# Sheet1.net
KiCad netlist of a schematic drawn in Altium Designer
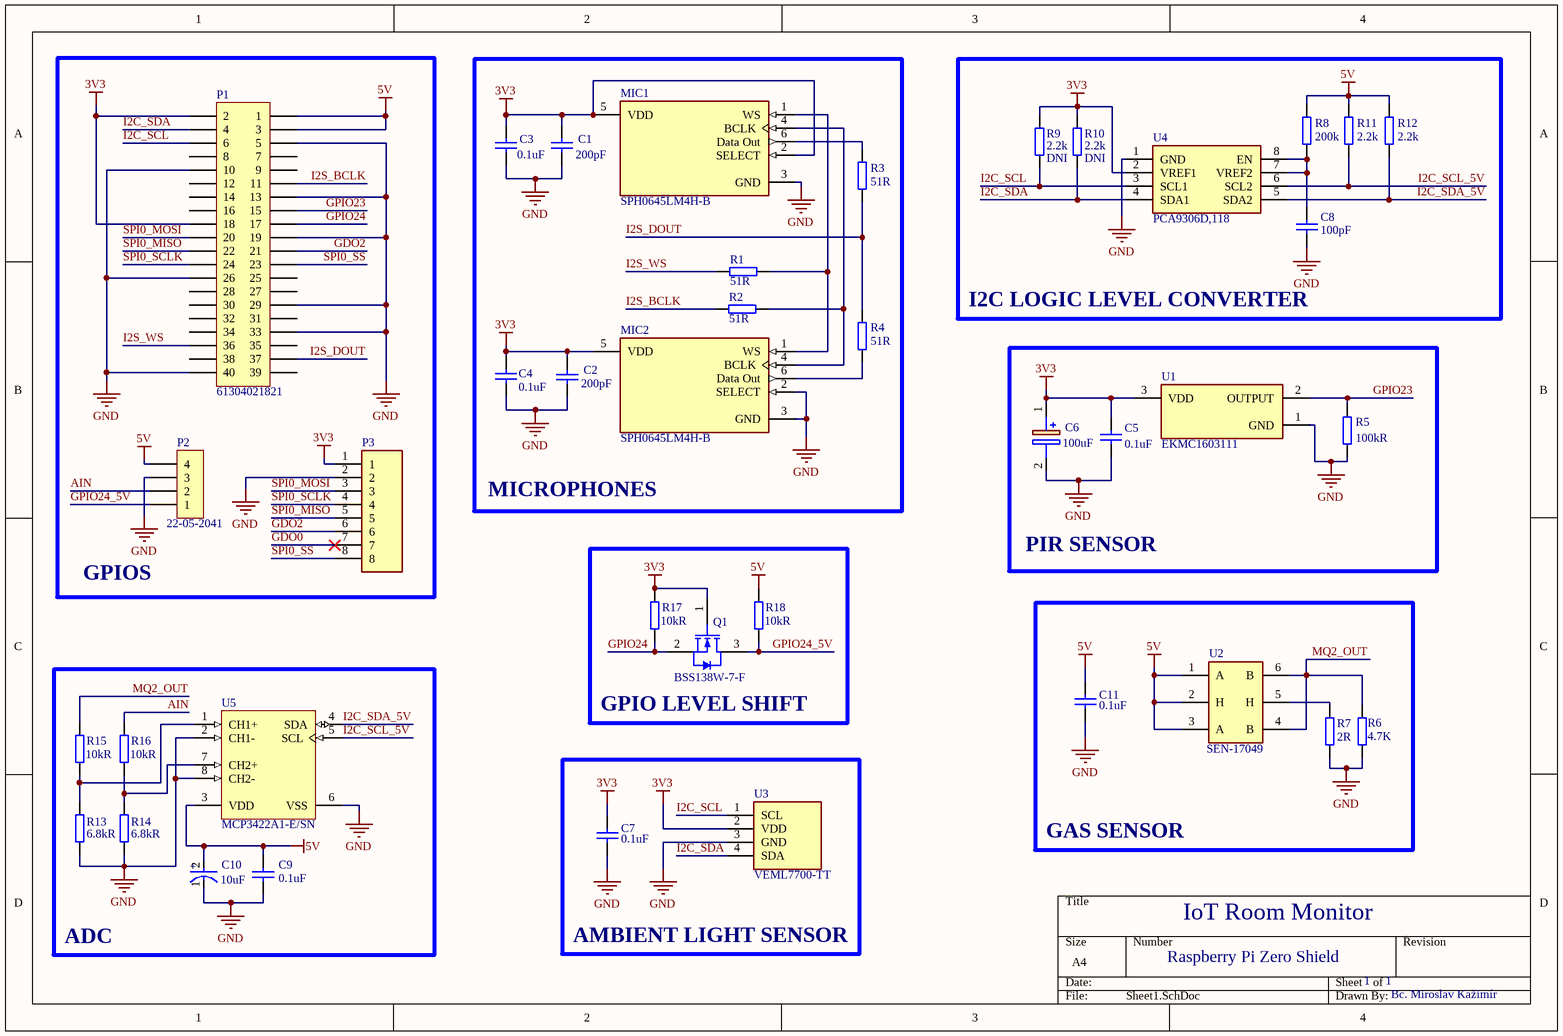
[diagram p0: Sheet1.SchDoc]

(export (version "E")
  (design (tool "Eeschema 10.0.6"))
  (components
    (comp (ref "C1")
      (value "C1206C201F4HACTU")
      (footprint "FP-C1206C-EB-MFG")
      (fields (field (name "MANUFACTURER") "KEMET") (field (name "CAPACITANCE") "200pF"))
      (libsource (lib "RPiZeroShield") (part "C1206C201F4HACTU"))
    )
    (comp (ref "C2")
      (value "C1206C201F4HACTU")
      (footprint "FP-C1206C-EB-MFG")
      (fields (field (name "MANUFACTURER") "KEMET") (field (name "CAPACITANCE") "200pF"))
      (libsource (lib "RPiZeroShield") (part "C1206C201F4HACTU"))
    )
    (comp (ref "C3")
      (value "GRM3195C1H104GA05D")
      (footprint "FP-GRM319-0_15-IPC_A")
      (description "Multi-Layer Ceramic Capacitor 0.1uF C0G 2% 1206 Paper T/R")
      (fields (field (name "MANUFACTURER") "Murata") (field (name "CAPACITANCE") "0.1uF"))
      (libsource (lib "RPiZeroShield") (part "GRM3195C1H104GA05D"))
    )
    (comp (ref "C4")
      (value "GRM3195C1H104GA05D")
      (footprint "FP-GRM319-0_15-IPC_A")
      (description "Multi-Layer Ceramic Capacitor 0.1uF C0G 2% 1206 Paper T/R")
      (fields (field (name "MANUFACTURER") "Murata") (field (name "CAPACITANCE") "0.1uF"))
      (libsource (lib "RPiZeroShield") (part "GRM3195C1H104GA05D"))
    )
    (comp (ref "C5")
      (value "GRM3195C1H104GA05D")
      (footprint "FP-GRM319-0_15-IPC_A")
      (description "Multi-Layer Ceramic Capacitor 0.1uF C0G 2% 1206 Paper T/R")
      (fields (field (name "MANUFACTURER") "Murata") (field (name "CAPACITANCE") "0.1uF"))
      (libsource (lib "RPiZeroShield") (part "GRM3195C1H104GA05D"))
    )
    (comp (ref "C6")
      (value "ECE-A0JKS101B")
      (footprint "CAPPRD250W50D630H600")
      (description "Cap Aluminum 100uF 6.3V 20% (6.3 X 5mm) Radial 5mm 71mA 1000 hr 85°C Ammo Pack")
      (fields
        (field (name "MANUFACTURER") "Panasonic")
        (field (name "CAPACITANCE") "100uF")
        (field (name "TOLERANCE") "20%")
      )
      (libsource (lib "RPiZeroShield") (part "ECE-A0JKS101B"))
    )
    (comp (ref "C7")
      (value "GRM3195C1H104GA05D")
      (footprint "FP-GRM319-0_15-IPC_A")
      (description "Multi-Layer Ceramic Capacitor 0.1uF C0G 2% 1206 Paper T/R")
      (fields (field (name "MANUFACTURER") "Murata") (field (name "CAPACITANCE") "0.1uF"))
      (libsource (lib "RPiZeroShield") (part "GRM3195C1H104GA05D"))
    )
    (comp (ref "C8")
      (value "C0805C101F3HACTU")
      (footprint "FP-C0805C-DN-IPC_A")
      (description "100.pf 25.0V Rohs Compliant: Yes")
      (fields (field (name "MANUFACTURER") "KEMET") (field (name "CAPACITANCE") "100pF"))
      (libsource (lib "RPiZeroShield") (part "C0805C101F3HACTU"))
    )
    (comp (ref "C9")
      (value "GRM3195C1H104GA05D")
      (footprint "FP-GRM319-0_15-IPC_A")
      (description "Multi-Layer Ceramic Capacitor 0.1uF C0G 2% 1206 Paper T/R")
      (fields (field (name "MANUFACTURER") "Murata") (field (name "CAPACITANCE") "0.1uF"))
      (libsource (lib "RPiZeroShield") (part "GRM3195C1H104GA05D"))
    )
    (comp (ref "C10")
      (value "T491A106K020AT")
      (footprint "FP-T491A106K020AT-MFG")
      (description "Cap Tant Solid 10uF 20V A CASE 10% (3.2 X 1.6 X 1.6mm) Inward L SMD 3216-18 5 Ohm 125°C T/R")
      (fields
        (field (name "MANUFACTURER") "KEMET")
        (field (name "CAPACITANCE") "10uF")
        (field (name "TOLERANCE") "10%")
      )
      (libsource (lib "RPiZeroShield") (part "T491A106K020AT"))
    )
    (comp (ref "C11")
      (value "GRM3195C1H104GA05D")
      (footprint "FP-GRM319-0_15-IPC_A")
      (description "Multi-Layer Ceramic Capacitor 0.1uF C0G 2% 1206 Paper T/R")
      (fields (field (name "MANUFACTURER") "Murata") (field (name "CAPACITANCE") "0.1uF"))
      (libsource (lib "RPiZeroShield") (part "GRM3195C1H104GA05D"))
    )
    (comp (ref "MIC1")
      (value "SPH0645LM4H-B")
      (footprint "FP-SPH0645LM4H-B-MFG")
      (description "Crawford Mic Dgt I2S Bottom Port")
      (fields (field (name "MANUFACTURER") "Knowles"))
      (libsource (lib "RPiZeroShield") (part "SPH0645LM4H-B"))
    )
    (comp (ref "MIC2")
      (value "SPH0645LM4H-B")
      (footprint "FP-SPH0645LM4H-B-MFG")
      (description "Crawford Mic Dgt I2S Bottom Port")
      (fields (field (name "MANUFACTURER") "Knowles"))
      (libsource (lib "RPiZeroShield") (part "SPH0645LM4H-B"))
    )
    (comp (ref "P1")
      (value "61304021821")
      (footprint "61304021821")
      (description "THT Vertical Socket Header WR-PHD, Pitch 2.54 mm, Dual Row, 40 pins")
      (fields (field (name "MANUFACTURER") "Wurth Electronics"))
      (libsource (lib "RPiZeroShield") (part "61304021821"))
    )
    (comp (ref "P2")
      (value "22-05-2041")
      (footprint "22052041")
      (description "Connector Unshrouded Header 4 Position 2.54mm Solder Right Angle Thru-Hole Bulk")
      (fields (field (name "MANUFACTURER") "Molex"))
      (libsource (lib "RPiZeroShield") (part "22-05-2041"))
    )
    (comp (ref "P3")
      (value "M22-2010805")
      (footprint "HDRV8W60P0X200_1X8_1600X200X525P")
      (description "Connector, Header, 8Pos, 1Row, 2Mm Rohs Compliant: Yes")
      (fields (field (name "MANUFACTURER") "Harwin"))
      (libsource (lib "RPiZeroShield") (part "M22-2010805"))
    )
    (comp (ref "Q1")
      (value "BSS138W-7-F")
      (footprint "DIOD-SOT323-3_V")
      (description "N沟道 VDS=50V VGS=±20V ID=200mA P=200mW")
      (fields (field (name "MANUFACTURER") "Diodes") (field (name "VOLTAGE") "50V"))
      (libsource (lib "RPiZeroShield") (part "BSS138W-7-F"))
    )
    (comp (ref "R1")
      (value "ERJ-6ENF51R0V")
      (footprint "RESC2013X70X40LL20T20")
      (description "贴片电阻 51Ω ±1% 1/8W ±100ppm/℃ 0805")
      (fields
        (field (name "MANUFACTURER") "Panasonic")
        (field (name "TOLERANCE") "1%")
        (field (name "RESISTANCE") "51R")
      )
      (libsource (lib "RPiZeroShield") (part "ERJ-6ENF51R0V"))
    )
    (comp (ref "R2")
      (value "ERJ-6ENF51R0V")
      (footprint "RESC2013X70X40LL20T20")
      (description "贴片电阻 51Ω ±1% 1/8W ±100ppm/℃ 0805")
      (fields
        (field (name "MANUFACTURER") "Panasonic")
        (field (name "TOLERANCE") "1%")
        (field (name "RESISTANCE") "51R")
      )
      (libsource (lib "RPiZeroShield") (part "ERJ-6ENF51R0V"))
    )
    (comp (ref "R3")
      (value "ERJ-6ENF51R0V")
      (footprint "RESC2013X70X40LL20T20")
      (description "贴片电阻 51Ω ±1% 1/8W ±100ppm/℃ 0805")
      (fields
        (field (name "MANUFACTURER") "Panasonic")
        (field (name "TOLERANCE") "1%")
        (field (name "RESISTANCE") "51R")
      )
      (libsource (lib "") (part "ERJ-6ENF51R0V_1"))
    )
    (comp (ref "R4")
      (value "ERJ-6ENF51R0V")
      (footprint "RESC2013X70X40LL20T20")
      (description "贴片电阻 51Ω ±1% 1/8W ±100ppm/℃ 0805")
      (fields
        (field (name "MANUFACTURER") "Panasonic")
        (field (name "TOLERANCE") "1%")
        (field (name "RESISTANCE") "51R")
      )
      (libsource (lib "") (part "ERJ-6ENF51R0V_2"))
    )
    (comp (ref "R5")
      (value "RC1206FR-07100KL")
      (footprint "RESC3116X65X40LL10T20")
      (description "贴片电阻 100000Ω ± 1.00% 0.25W ± 100ppm/℃ 1206")
      (fields
        (field (name "MANUFACTURER") "Yageo")
        (field (name "TOLERANCE") "1%")
        (field (name "RESISTANCE") "100kR")
      )
      (libsource (lib "RPiZeroShield") (part "RC1206FR-07100KL"))
    )
    (comp (ref "R6")
      (value "RCC12064K70FKEA")
      (footprint "RCC1206_e3")
      (description "Res, 4K7, 1%, 0.5W, 1206, Thick Film;")
      (fields (field (name "MANUFACTURER") "Vishay") (field (name "RESISTANCE") "4.7K"))
      (libsource (lib "RPiZeroShield") (part "RCC12064K70FKEA"))
    )
    (comp (ref "R7")
      (value "RC1206JR-7W2RL")
      (footprint "RESC3116X65N")
      (description "Res Thick Film 1206 2 Ohm 5% 0.5W(1/2W) ±200ppm/C Pad SMD T/R")
      (fields
        (field (name "MANUFACTURER") "Yageo")
        (field (name "RESISTANCE") "2R")
        (field (name "TOLERANCE") "5%")
      )
      (libsource (lib "RPiZeroShield") (part "RC1206JR-7W2RL"))
    )
    (comp (ref "R8")
      (value "RCC1206200KFKEA")
      (footprint "RCC1206_e3")
      (description "Res, AEC-Q200, 200K, 1%, 0.5W, 1206 Rohs Compliant: Yes")
      (fields (field (name "MANUFACTURER") "Vishay") (field (name "RESISTANCE") "200k"))
      (libsource (lib "RPiZeroShield") (part "RCC1206200KFKEA"))
    )
    (comp (ref "R9")
      (value "RCC12062K20FKEA")
      (footprint "RCC1206_e3")
      (description "Res, Aec-Q200, 2K2, 1%, 0.5W, 1206 Rohs Compliant: Yes")
      (fields (field (name "MANUFACTURER") "Vishay") (field (name "RESISTANCE") "2.2k"))
      (libsource (lib "RPiZeroShield") (part "RCC12062K20FKEA"))
    )
    (comp (ref "R10")
      (value "RCC12062K20FKEA")
      (footprint "RCC1206_e3")
      (description "Res, Aec-Q200, 2K2, 1%, 0.5W, 1206 Rohs Compliant: Yes")
      (fields (field (name "MANUFACTURER") "Vishay") (field (name "RESISTANCE") "2.2k"))
      (libsource (lib "RPiZeroShield") (part "RCC12062K20FKEA"))
    )
    (comp (ref "R11")
      (value "RCC12062K20FKEA")
      (footprint "RCC1206_e3")
      (description "Res, Aec-Q200, 2K2, 1%, 0.5W, 1206 Rohs Compliant: Yes")
      (fields (field (name "MANUFACTURER") "Vishay") (field (name "RESISTANCE") "2.2k"))
      (libsource (lib "RPiZeroShield") (part "RCC12062K20FKEA"))
    )
    (comp (ref "R12")
      (value "RCC12062K20FKEA")
      (footprint "RCC1206_e3")
      (description "Res, Aec-Q200, 2K2, 1%, 0.5W, 1206 Rohs Compliant: Yes")
      (fields (field (name "MANUFACTURER") "Vishay") (field (name "RESISTANCE") "2.2k"))
      (libsource (lib "RPiZeroShield") (part "RCC12062K20FKEA"))
    )
    (comp (ref "R13")
      (value "ERJ-P06D6801V")
      (footprint "ERJP06_(0805)")
      (description "Res Thick Film 0805 6.8K Ohm 0.5% 0.25W ±100ppm/°C Molded SMD Punched Carrier T/R")
      (fields
        (field (name "MANUFACTURER") "Panasonic")
        (field (name "RESISTANCE") "6.8kR")
        (field (name "TOLERANCE") "0.5%")
      )
      (libsource (lib "RPiZeroShield") (part "ERJ-P06D6801V"))
    )
    (comp (ref "R14")
      (value "ERJ-P06D6801V")
      (footprint "ERJP06_(0805)")
      (description "Res Thick Film 0805 6.8K Ohm 0.5% 0.25W ±100ppm/°C Molded SMD Punched Carrier T/R")
      (fields
        (field (name "MANUFACTURER") "Panasonic")
        (field (name "RESISTANCE") "6.8kR")
        (field (name "TOLERANCE") "0.5%")
      )
      (libsource (lib "RPiZeroShield") (part "ERJ-P06D6801V"))
    )
    (comp (ref "R15")
      (value "ERJ-P08D1002V")
      (footprint "ERJP08_(1206)")
      (description "Res Thick Film 1206 10K Ohm 0.5% 0.33W ±100ppm/°C Molded SMD Punched Carrier T/R")
      (fields
        (field (name "MANUFACTURER") "Panasonic")
        (field (name "RESISTANCE") "10kR")
        (field (name "TOLERANCE") "0.5%")
      )
      (libsource (lib "RPiZeroShield") (part "ERJ-P08D1002V"))
    )
    (comp (ref "R16")
      (value "ERJ-P08D1002V")
      (footprint "ERJP08_(1206)")
      (description "Res Thick Film 1206 10K Ohm 0.5% 0.33W ±100ppm/°C Molded SMD Punched Carrier T/R")
      (fields
        (field (name "MANUFACTURER") "Panasonic")
        (field (name "RESISTANCE") "10kR")
        (field (name "TOLERANCE") "0.5%")
      )
      (libsource (lib "RPiZeroShield") (part "ERJ-P08D1002V"))
    )
    (comp (ref "R17")
      (value "ERJ-P08D1002V")
      (footprint "ERJP08_(1206)")
      (description "Res Thick Film 1206 10K Ohm 0.5% 0.33W ±100ppm/°C Molded SMD Punched Carrier T/R")
      (fields
        (field (name "MANUFACTURER") "Panasonic")
        (field (name "RESISTANCE") "10kR")
        (field (name "TOLERANCE") "0.5%")
      )
      (libsource (lib "RPiZeroShield") (part "ERJ-P08D1002V"))
    )
    (comp (ref "R18")
      (value "ERJ-P08D1002V")
      (footprint "ERJP08_(1206)")
      (description "Res Thick Film 1206 10K Ohm 0.5% 0.33W ±100ppm/°C Molded SMD Punched Carrier T/R")
      (fields
        (field (name "MANUFACTURER") "Panasonic")
        (field (name "RESISTANCE") "10kR")
        (field (name "TOLERANCE") "0.5%")
      )
      (libsource (lib "RPiZeroShield") (part "ERJ-P08D1002V"))
    )
    (comp (ref "U1")
      (value "EKMC1603111")
      (footprint "FP-EKMC1603111-MFG")
      (description "PaPIRs MOTION SENSOR VZ series 170uA (White) 12m detection range")
      (fields (field (name "MANUFACTURER") "Panasonic"))
      (libsource (lib "RPiZeroShield") (part "EKMC1603111"))
    )
    (comp (ref "U2")
      (value "SEN-17049")
      (footprint "SEN17049")
      (description "Smoke Sensor - MQ-2")
      (fields (field (name "MANUFACTURER") "SparkFun"))
      (libsource (lib "RPiZeroShield") (part "SEN-17049"))
    )
    (comp (ref "U3")
      (value "VEML7700-TT")
      (footprint "VEML7700")
      (description "Light to Digital Ambient Light Sensor Digital 0lux to 167000lux 8-Pin SMD T/R")
      (fields (field (name "MANUFACTURER") "Vishay Semiconductors"))
      (libsource (lib "RPiZeroShield") (part "VEML7700-TT"))
    )
    (comp (ref "U4")
      (value "PCA9306D,118")
      (footprint "SOIC127P600X175-8N")
      (description "PCA9306 Series 3.3 V Dual Bidirectional Voltage-Level Translator - SOIC-8")
      (fields (field (name "MANUFACTURER") "NXP Semiconductors"))
      (libsource (lib "RPiZeroShield") (part "PCA9306D,118"))
    )
    (comp (ref "U5")
      (value "MCP3422A1-E/SN")
      (footprint "SOIC-SN8_N")
      (description "2-Channel Single ADC Delta-Sigma 3.75sps 18-bit Serial Automotive 8-Pin SOIC N Tube")
      (fields (field (name "MANUFACTURER") "Microchip"))
      (libsource (lib "RPiZeroShield") (part "MCP3422A1-E/SN"))
    )
  )
  (nets
    (net (code "1") (name "/AIN") (class "Default")
      (node (ref "P2") (pin "2") (pinfunction "2_2") (pintype "passive"))
      (node (ref "R16") (pin "1") (pinfunction "1_1") (pintype "passive"))
    )
    (net (code "2") (name "/GDO0") (class "Default")
      (node (ref "P3") (pin "7") (pinfunction "7_7") (pintype "passive+no_connect"))
    )
    (net (code "3") (name "/GDO2") (class "Default")
      (node (ref "P1") (pin "21") (pinfunction "21_21") (pintype "passive"))
      (node (ref "P3") (pin "6") (pinfunction "6_6") (pintype "passive"))
    )
    (net (code "4") (name "/GPIO23") (class "Default")
      (node (ref "P1") (pin "15") (pinfunction "15_15") (pintype "passive"))
      (node (ref "R5") (pin "1") (pinfunction "1_1") (pintype "passive"))
      (node (ref "U1") (pin "2") (pinfunction "OUTPUT_2") (pintype "open_collector"))
    )
    (net (code "5") (name "/GPIO24") (class "Default")
      (node (ref "P1") (pin "17") (pinfunction "17_17") (pintype "passive"))
      (node (ref "Q1") (pin "2") (pinfunction "S_2") (pintype "passive"))
      (node (ref "R17") (pin "2") (pinfunction "2_2") (pintype "passive"))
    )
    (net (code "6") (name "/GPIO24_5V") (class "Default")
      (node (ref "P2") (pin "1") (pinfunction "1_1") (pintype "passive"))
      (node (ref "Q1") (pin "3") (pinfunction "D_3") (pintype "passive"))
      (node (ref "R18") (pin "2") (pinfunction "2_2") (pintype "passive"))
    )
    (net (code "7") (name "/I2C_SCL") (class "Default")
      (node (ref "P1") (pin "6") (pinfunction "6_6") (pintype "passive"))
      (node (ref "R9") (pin "2") (pinfunction "2_2") (pintype "passive"))
      (node (ref "U3") (pin "1") (pinfunction "SCL_1") (pintype "passive"))
      (node (ref "U4") (pin "3") (pinfunction "SCL1_3") (pintype "passive"))
    )
    (net (code "8") (name "/I2C_SCL_5V") (class "Default")
      (node (ref "R11") (pin "2") (pinfunction "2_2") (pintype "passive"))
      (node (ref "U4") (pin "6") (pinfunction "SCL2_6") (pintype "passive"))
      (node (ref "U5") (pin "5") (pinfunction "SCL_5") (pintype "input"))
    )
    (net (code "9") (name "/I2C_SDA") (class "Default")
      (node (ref "P1") (pin "4") (pinfunction "4_4") (pintype "passive"))
      (node (ref "R10") (pin "2") (pinfunction "2_2") (pintype "passive"))
      (node (ref "U3") (pin "4") (pinfunction "SDA_4") (pintype "passive"))
      (node (ref "U4") (pin "4") (pinfunction "SDA1_4") (pintype "passive"))
    )
    (net (code "10") (name "/I2C_SDA_5V") (class "Default")
      (node (ref "R12") (pin "2") (pinfunction "2_2") (pintype "passive"))
      (node (ref "U4") (pin "5") (pinfunction "SDA2_5") (pintype "passive"))
      (node (ref "U5") (pin "4") (pinfunction "SDA_4") (pintype "bidirectional"))
    )
    (net (code "11") (name "/I2S_BCLK") (class "Default")
      (node (ref "P1") (pin "11") (pinfunction "11_11") (pintype "passive"))
      (node (ref "R2") (pin "1") (pinfunction "1_1") (pintype "passive"))
    )
    (net (code "12") (name "/I2S_DOUT") (class "Default")
      (node (ref "P1") (pin "37") (pinfunction "37_37") (pintype "passive"))
      (node (ref "R3") (pin "2") (pinfunction "2_2") (pintype "passive"))
      (node (ref "R4") (pin "2") (pinfunction "2_2") (pintype "passive"))
    )
    (net (code "13") (name "/I2S_WS") (class "Default")
      (node (ref "P1") (pin "36") (pinfunction "36_36") (pintype "passive"))
      (node (ref "R1") (pin "1") (pinfunction "1_1") (pintype "passive"))
    )
    (net (code "14") (name "/MQ2_OUT") (class "Default")
      (node (ref "R15") (pin "1") (pinfunction "1_1") (pintype "passive"))
      (node (ref "R6") (pin "2") (pinfunction "2_2") (pintype "passive"))
      (node (ref "U2") (pin "4") (pinfunction "B_4") (pintype "passive"))
      (node (ref "U2") (pin "6") (pinfunction "B_6") (pintype "passive"))
    )
    (net (code "15") (name "/SPI0_MISO") (class "Default")
      (node (ref "P1") (pin "22") (pinfunction "22_22") (pintype "passive"))
      (node (ref "P3") (pin "5") (pinfunction "5_5") (pintype "passive"))
    )
    (net (code "16") (name "/SPI0_MOSI") (class "Default")
      (node (ref "P1") (pin "20") (pinfunction "20_20") (pintype "passive"))
      (node (ref "P3") (pin "3") (pinfunction "3_3") (pintype "passive"))
    )
    (net (code "17") (name "/SPI0_SCLK") (class "Default")
      (node (ref "P1") (pin "24") (pinfunction "24_24") (pintype "passive"))
      (node (ref "P3") (pin "4") (pinfunction "4_4") (pintype "passive"))
    )
    (net (code "18") (name "/SPI0_SS") (class "Default")
      (node (ref "P1") (pin "23") (pinfunction "23_23") (pintype "passive"))
      (node (ref "P3") (pin "8") (pinfunction "8_8") (pintype "passive"))
    )
    (net (code "19") (name "3V3") (class "Default")
      (node (ref "C1") (pin "1") (pinfunction "1_1") (pintype "passive"))
      (node (ref "C2") (pin "1") (pinfunction "1_1") (pintype "passive"))
      (node (ref "C3") (pin "2") (pinfunction "2_2") (pintype "passive"))
      (node (ref "C4") (pin "2") (pinfunction "2_2") (pintype "passive"))
      (node (ref "C5") (pin "2") (pinfunction "2_2") (pintype "passive"))
      (node (ref "C6") (pin "1") (pinfunction "+_1") (pintype "passive"))
      (node (ref "C7") (pin "1") (pinfunction "1_1") (pintype "passive"))
      (node (ref "MIC1") (pin "2") (pinfunction "SELECT_2") (pintype "input"))
      (node (ref "MIC1") (pin "5") (pinfunction "VDD_5") (pintype "power_in"))
      (node (ref "MIC2") (pin "5") (pinfunction "VDD_5") (pintype "power_in"))
      (node (ref "P1") (pin "18") (pinfunction "18_18") (pintype "passive"))
      (node (ref "P1") (pin "2") (pinfunction "2_2") (pintype "passive"))
      (node (ref "P3") (pin "1") (pinfunction "1_1") (pintype "passive"))
      (node (ref "Q1") (pin "1") (pinfunction "G_1") (pintype "passive"))
      (node (ref "R10") (pin "1") (pinfunction "1_1") (pintype "passive"))
      (node (ref "R17") (pin "1") (pinfunction "1_1") (pintype "passive"))
      (node (ref "R9") (pin "1") (pinfunction "1_1") (pintype "passive"))
      (node (ref "U1") (pin "3") (pinfunction "VDD_3") (pintype "power_in"))
      (node (ref "U3") (pin "2") (pinfunction "VDD_2") (pintype "passive"))
      (node (ref "U4") (pin "2") (pinfunction "VREF1_2") (pintype "passive"))
    )
    (net (code "20") (name "5V") (class "Default")
      (node (ref "C10") (pin "2") (pinfunction "A_2") (pintype "passive"))
      (node (ref "C11") (pin "1") (pinfunction "1_1") (pintype "passive"))
      (node (ref "C9") (pin "1") (pinfunction "1_1") (pintype "passive"))
      (node (ref "P1") (pin "1") (pinfunction "1_1") (pintype "passive"))
      (node (ref "P1") (pin "3") (pinfunction "3_3") (pintype "passive"))
      (node (ref "P2") (pin "4") (pinfunction "4_4") (pintype "passive"))
      (node (ref "R11") (pin "1") (pinfunction "1_1") (pintype "passive"))
      (node (ref "R12") (pin "1") (pinfunction "1_1") (pintype "passive"))
      (node (ref "R18") (pin "1") (pinfunction "1_1") (pintype "passive"))
      (node (ref "R8") (pin "2") (pinfunction "2_2") (pintype "passive"))
      (node (ref "U2") (pin "1") (pinfunction "A_1") (pintype "passive"))
      (node (ref "U2") (pin "2") (pinfunction "H_2") (pintype "passive"))
      (node (ref "U2") (pin "3") (pinfunction "A_3") (pintype "passive"))
      (node (ref "U5") (pin "3") (pinfunction "VDD_3") (pintype "power_in"))
    )
    (net (code "21") (name "GND") (class "Default")
      (node (ref "C1") (pin "2") (pinfunction "2_2") (pintype "passive"))
      (node (ref "C10") (pin "1") (pinfunction "C_1") (pintype "passive"))
      (node (ref "C11") (pin "2") (pinfunction "2_2") (pintype "passive"))
      (node (ref "C2") (pin "2") (pinfunction "2_2") (pintype "passive"))
      (node (ref "C3") (pin "1") (pinfunction "1_1") (pintype "passive"))
      (node (ref "C4") (pin "1") (pinfunction "1_1") (pintype "passive"))
      (node (ref "C5") (pin "1") (pinfunction "1_1") (pintype "passive"))
      (node (ref "C6") (pin "2") (pinfunction "-_2") (pintype "passive"))
      (node (ref "C7") (pin "2") (pinfunction "2_2") (pintype "passive"))
      (node (ref "C8") (pin "2") (pinfunction "2_2") (pintype "passive"))
      (node (ref "C9") (pin "2") (pinfunction "2_2") (pintype "passive"))
      (node (ref "MIC1") (pin "3") (pinfunction "GND_3") (pintype "power_in"))
      (node (ref "MIC2") (pin "2") (pinfunction "SELECT_2") (pintype "input"))
      (node (ref "MIC2") (pin "3") (pinfunction "GND_3") (pintype "power_in"))
      (node (ref "P1") (pin "10") (pinfunction "10_10") (pintype "passive"))
      (node (ref "P1") (pin "13") (pinfunction "13_13") (pintype "passive"))
      (node (ref "P1") (pin "19") (pinfunction "19_19") (pintype "passive"))
      (node (ref "P1") (pin "26") (pinfunction "26_26") (pintype "passive"))
      (node (ref "P1") (pin "29") (pinfunction "29_29") (pintype "passive"))
      (node (ref "P1") (pin "33") (pinfunction "33_33") (pintype "passive"))
      (node (ref "P1") (pin "40") (pinfunction "40_40") (pintype "passive"))
      (node (ref "P1") (pin "5") (pinfunction "5_5") (pintype "passive"))
      (node (ref "P2") (pin "3") (pinfunction "3_3") (pintype "passive"))
      (node (ref "P3") (pin "2") (pinfunction "2_2") (pintype "passive"))
      (node (ref "R13") (pin "2") (pinfunction "2_2") (pintype "passive"))
      (node (ref "R14") (pin "2") (pinfunction "2_2") (pintype "passive"))
      (node (ref "R5") (pin "2") (pinfunction "2_2") (pintype "passive"))
      (node (ref "R6") (pin "1") (pinfunction "1_1") (pintype "passive"))
      (node (ref "R7") (pin "2") (pinfunction "2_2") (pintype "passive"))
      (node (ref "U1") (pin "1") (pinfunction "GND_1") (pintype "power_in"))
      (node (ref "U3") (pin "3") (pinfunction "GND_3") (pintype "passive"))
      (node (ref "U4") (pin "1") (pinfunction "GND_1") (pintype "passive"))
      (node (ref "U5") (pin "2") (pinfunction "CH1-_2") (pintype "input"))
      (node (ref "U5") (pin "6") (pinfunction "VSS_6") (pintype "power_in"))
      (node (ref "U5") (pin "8") (pinfunction "CH2-_8") (pintype "input"))
    )
    (net (code "22") (name "Net-(MIC1-BCLK)") (class "Default")
      (node (ref "MIC1") (pin "4") (pinfunction "BCLK_4") (pintype "input"))
      (node (ref "MIC2") (pin "4") (pinfunction "BCLK_4") (pintype "input"))
      (node (ref "R2") (pin "2") (pinfunction "2_2") (pintype "passive"))
    )
    (net (code "23") (name "Net-(MIC1-Data_Out)") (class "Default")
      (node (ref "MIC1") (pin "6") (pinfunction "Data_Out_6") (pintype "output"))
      (node (ref "R3") (pin "1") (pinfunction "1_1") (pintype "passive"))
    )
    (net (code "24") (name "Net-(MIC1-WS)") (class "Default")
      (node (ref "MIC1") (pin "1") (pinfunction "WS_1") (pintype "input"))
      (node (ref "MIC2") (pin "1") (pinfunction "WS_1") (pintype "input"))
      (node (ref "R1") (pin "2") (pinfunction "2_2") (pintype "passive"))
    )
    (net (code "25") (name "Net-(MIC2-Data_Out)") (class "Default")
      (node (ref "MIC2") (pin "6") (pinfunction "Data_Out_6") (pintype "output"))
      (node (ref "R4") (pin "1") (pinfunction "1_1") (pintype "passive"))
    )
    (net (code "26") (name "Net-(R7-Pad1)") (class "Default")
      (node (ref "R7") (pin "1") (pinfunction "1_1") (pintype "passive"))
      (node (ref "U2") (pin "5") (pinfunction "H_5") (pintype "passive"))
    )
    (net (code "27") (name "Net-(U4-EN)") (class "Default")
      (node (ref "C8") (pin "1") (pinfunction "1_1") (pintype "passive"))
      (node (ref "R8") (pin "1") (pinfunction "1_1") (pintype "passive"))
      (node (ref "U4") (pin "7") (pinfunction "VREF2_7") (pintype "passive"))
      (node (ref "U4") (pin "8") (pinfunction "EN_8") (pintype "passive"))
    )
    (net (code "28") (name "Net-(U5-CH1+)") (class "Default")
      (node (ref "R13") (pin "1") (pinfunction "1_1") (pintype "passive"))
      (node (ref "R15") (pin "2") (pinfunction "2_2") (pintype "passive"))
      (node (ref "U5") (pin "1") (pinfunction "CH1+_1") (pintype "input"))
    )
    (net (code "29") (name "Net-(U5-CH2+)") (class "Default")
      (node (ref "R14") (pin "1") (pinfunction "1_1") (pintype "passive"))
      (node (ref "R16") (pin "2") (pinfunction "2_2") (pintype "passive"))
      (node (ref "U5") (pin "7") (pinfunction "CH2+_7") (pintype "input"))
    )
    (net (code "30") (name "unconnected-(P1-Pad7)") (class "Default")
      (node (ref "P1") (pin "7") (pinfunction "7_7") (pintype "passive"))
    )
    (net (code "31") (name "unconnected-(P1-Pad8)") (class "Default")
      (node (ref "P1") (pin "8") (pinfunction "8_8") (pintype "passive"))
    )
    (net (code "32") (name "unconnected-(P1-Pad9)") (class "Default")
      (node (ref "P1") (pin "9") (pinfunction "9_9") (pintype "passive"))
    )
    (net (code "33") (name "unconnected-(P1-Pad12)") (class "Default")
      (node (ref "P1") (pin "12") (pinfunction "12_12") (pintype "passive"))
    )
    (net (code "34") (name "unconnected-(P1-Pad14)") (class "Default")
      (node (ref "P1") (pin "14") (pinfunction "14_14") (pintype "passive"))
    )
    (net (code "35") (name "unconnected-(P1-Pad16)") (class "Default")
      (node (ref "P1") (pin "16") (pinfunction "16_16") (pintype "passive"))
    )
    (net (code "36") (name "unconnected-(P1-Pad25)") (class "Default")
      (node (ref "P1") (pin "25") (pinfunction "25_25") (pintype "passive"))
    )
    (net (code "37") (name "unconnected-(P1-Pad27)") (class "Default")
      (node (ref "P1") (pin "27") (pinfunction "27_27") (pintype "passive"))
    )
    (net (code "38") (name "unconnected-(P1-Pad28)") (class "Default")
      (node (ref "P1") (pin "28") (pinfunction "28_28") (pintype "passive"))
    )
    (net (code "39") (name "unconnected-(P1-Pad30)") (class "Default")
      (node (ref "P1") (pin "30") (pinfunction "30_30") (pintype "passive"))
    )
    (net (code "40") (name "unconnected-(P1-Pad31)") (class "Default")
      (node (ref "P1") (pin "31") (pinfunction "31_31") (pintype "passive"))
    )
    (net (code "41") (name "unconnected-(P1-Pad32)") (class "Default")
      (node (ref "P1") (pin "32") (pinfunction "32_32") (pintype "passive"))
    )
    (net (code "42") (name "unconnected-(P1-Pad34)") (class "Default")
      (node (ref "P1") (pin "34") (pinfunction "34_34") (pintype "passive"))
    )
    (net (code "43") (name "unconnected-(P1-Pad35)") (class "Default")
      (node (ref "P1") (pin "35") (pinfunction "35_35") (pintype "passive"))
    )
    (net (code "44") (name "unconnected-(P1-Pad38)") (class "Default")
      (node (ref "P1") (pin "38") (pinfunction "38_38") (pintype "passive"))
    )
    (net (code "45") (name "unconnected-(P1-Pad39)") (class "Default")
      (node (ref "P1") (pin "39") (pinfunction "39_39") (pintype "passive"))
    )
  )
)
